# 02_LAN7800_Controller.net
KiCad netlist of a schematic drawn in Altium Designer
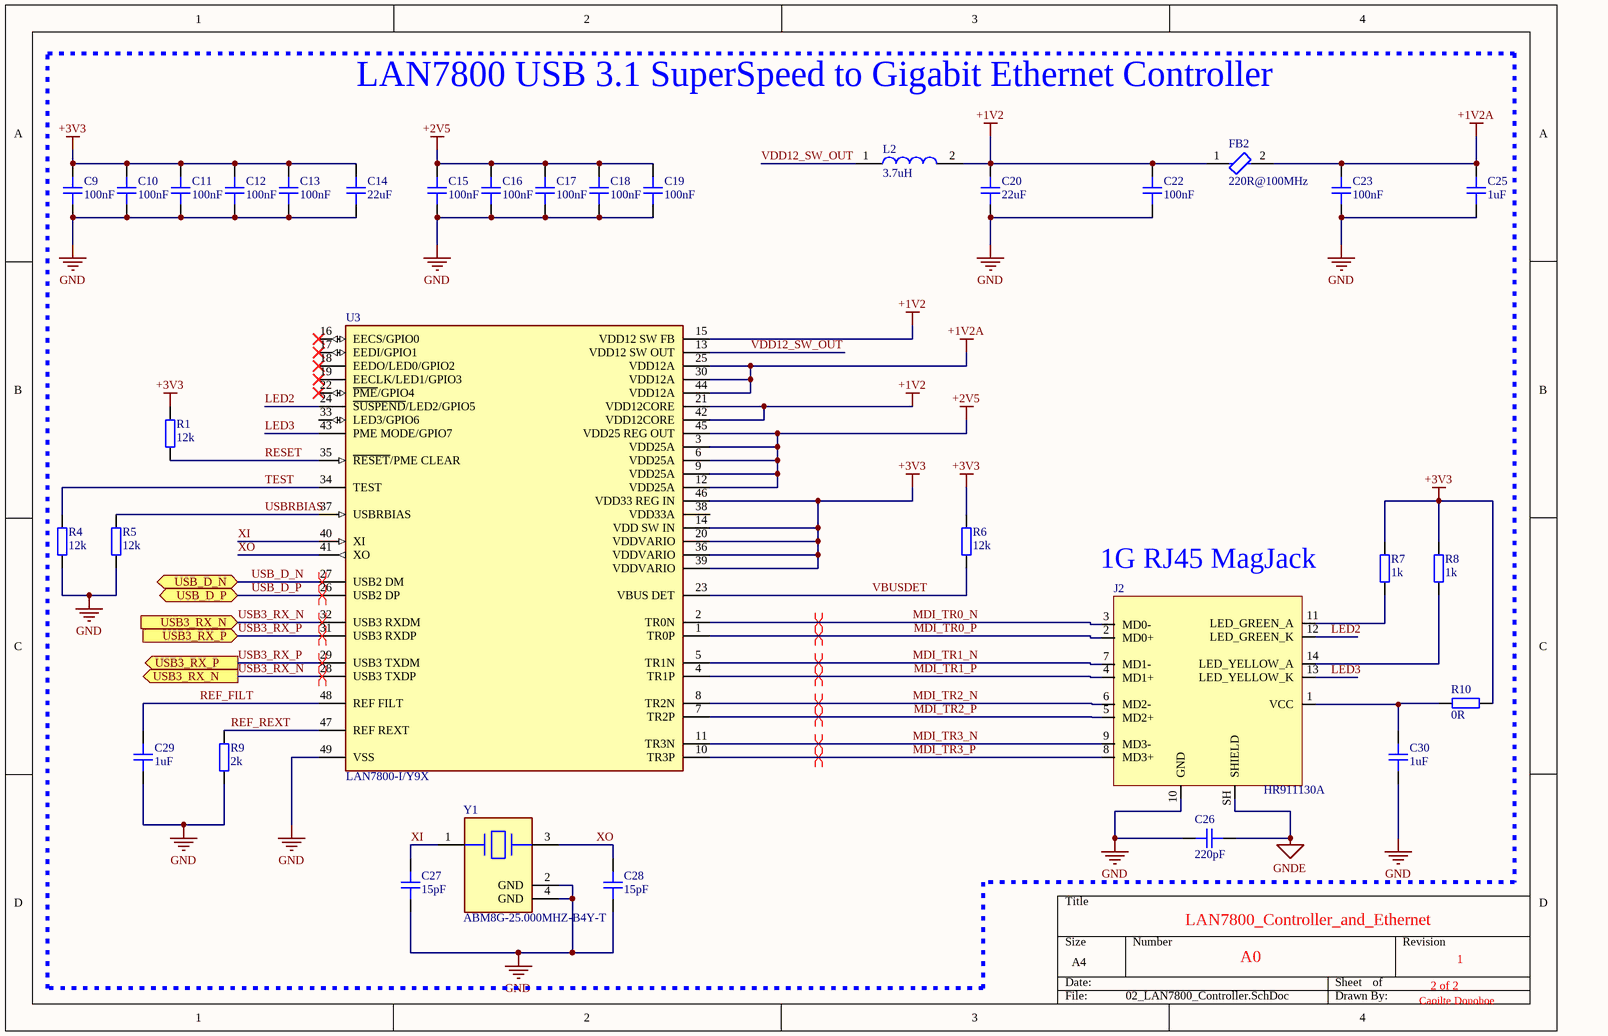
[diagram p0: 02_LAN7800_Controller.SchDoc]

(export (version "E")
  (design (tool "Eeschema 10.0.6"))
  (components
    (comp (ref "C9")
      (value "100nF")
      (footprint "CAP_0402")
      (description "Capacitor SMD 0402")
      (libsource (lib "Schematic-Lib-PMS_Caoilte") (part "CAP_0402"))
    )
    (comp (ref "C10")
      (value "100nF")
      (footprint "CAP_0402")
      (description "Capacitor SMD 0402")
      (libsource (lib "Schematic-Lib-PMS_Caoilte") (part "CAP_0402"))
    )
    (comp (ref "C11")
      (value "100nF")
      (footprint "CAP_0402")
      (description "Capacitor SMD 0402")
      (libsource (lib "Schematic-Lib-PMS_Caoilte") (part "CAP_0402"))
    )
    (comp (ref "C12")
      (value "100nF")
      (footprint "CAP_0402")
      (description "Capacitor SMD 0402")
      (libsource (lib "Schematic-Lib-PMS_Caoilte") (part "CAP_0402"))
    )
    (comp (ref "C13")
      (value "100nF")
      (footprint "CAP_0402")
      (description "Capacitor SMD 0402")
      (libsource (lib "Schematic-Lib-PMS_Caoilte") (part "CAP_0402"))
    )
    (comp (ref "C14")
      (value "22uF")
      (footprint "CAP_0603")
      (description "Capacitor SMD 0603")
      (libsource (lib "Schematic-Lib-PMS_Caoilte") (part "CAP_0603"))
    )
    (comp (ref "C15")
      (value "100nF")
      (footprint "CAP_0402")
      (description "Capacitor SMD 0402")
      (libsource (lib "Schematic-Lib-PMS_Caoilte") (part "CAP_0402"))
    )
    (comp (ref "C16")
      (value "100nF")
      (footprint "CAP_0402")
      (description "Capacitor SMD 0402")
      (libsource (lib "Schematic-Lib-PMS_Caoilte") (part "CAP_0402"))
    )
    (comp (ref "C17")
      (value "100nF")
      (footprint "CAP_0402")
      (description "Capacitor SMD 0402")
      (libsource (lib "Schematic-Lib-PMS_Caoilte") (part "CAP_0402"))
    )
    (comp (ref "C18")
      (value "100nF")
      (footprint "CAP_0402")
      (description "Capacitor SMD 0402")
      (libsource (lib "Schematic-Lib-PMS_Caoilte") (part "CAP_0402"))
    )
    (comp (ref "C19")
      (value "100nF")
      (footprint "CAP_0402")
      (description "Capacitor SMD 0402")
      (libsource (lib "Schematic-Lib-PMS_Caoilte") (part "CAP_0402"))
    )
    (comp (ref "C20")
      (value "22uF")
      (footprint "CAP_0603")
      (description "Capacitor SMD 0603")
      (libsource (lib "Schematic-Lib-PMS_Caoilte") (part "CAP_0603"))
    )
    (comp (ref "C22")
      (value "100nF")
      (footprint "CAP_0402")
      (description "Capacitor SMD 0402")
      (libsource (lib "Schematic-Lib-PMS_Caoilte") (part "CAP_0402"))
    )
    (comp (ref "C23")
      (value "100nF")
      (footprint "CAP_0402")
      (description "Capacitor SMD 0402")
      (libsource (lib "Schematic-Lib-PMS_Caoilte") (part "CAP_0402"))
    )
    (comp (ref "C25")
      (value "1uF")
      (footprint "CAP_0402")
      (description "Capacitor SMD 0402")
      (libsource (lib "Schematic-Lib-PMS_Caoilte") (part "CAP_0402"))
    )
    (comp (ref "C26")
      (value "220pF")
      (footprint "CAP_0603")
      (description "Capacitor SMD 0603")
      (libsource (lib "Schematic-Lib-PMS_Caoilte") (part "CAP_0603"))
    )
    (comp (ref "C27")
      (value "15pF")
      (footprint "CAP_0603")
      (description "Capacitor SMD 0603")
      (libsource (lib "Schematic-Lib-PMS_Caoilte") (part "CAP_0603"))
    )
    (comp (ref "C28")
      (value "15pF")
      (footprint "CAP_0603")
      (description "Capacitor SMD 0603")
      (libsource (lib "Schematic-Lib-PMS_Caoilte") (part "CAP_0603"))
    )
    (comp (ref "C29")
      (value "1uF")
      (footprint "CAP_0402")
      (description "Capacitor SMD 0402")
      (libsource (lib "Schematic-Lib-PMS_Caoilte") (part "CAP_0402"))
    )
    (comp (ref "C30")
      (value "1uF")
      (footprint "CAP_0402")
      (description "Capacitor SMD 0402")
      (libsource (lib "Schematic-Lib-PMS_Caoilte") (part "CAP_0402"))
    )
    (comp (ref "FB2")
      (value "220R@100MHz")
      (footprint "FP-BLM21-0_2-t0_85-e0_5-IPC_C")
      (description "Chip Ferrite Bead, 0805, 220Ω @ 100MHz, 0.045Ω, 25%, 2A")
      (fields (field (name "TOLERANCE") "25%"))
      (libsource (lib "LAN7800_USB_Ethernet_RevA") (part "CMP-0686-00610-3"))
    )
    (comp (ref "J2")
      (value "HR911130A")
      (footprint "HR911130A")
      (description "100/1000Base-T Magnetics Single-Port RJ45 Connector with Integrated Magnetics and LEDs")
      (fields (field (name "MANUFACTURER") "Hanrun"))
      (libsource (lib "LAN7800_USB_Ethernet_RevA") (part "HR911130A"))
    )
    (comp (ref "L2")
      (value "3.7uH")
      (footprint "SamacSys:LQM18PH1R0MFRB")
      (description "Inductor")
      (fields
        (field (name "MANUFACTURER_PART_NUMBER") "LQM18PN3R3MFRL")
        (field (name "MOUSER PART NUMBER") "81-LQM18PN3R3MFRL")
      )
      (libsource (lib "LAN7800_USB_Ethernet_RevA") (part "LQM18PN3R3MFRL"))
    )
    (comp (ref "R1")
      (value "12k")
      (footprint "RES_0402")
      (description "Resistor SMD 0402")
      (libsource (lib "Schematic-Lib-PMS_Caoilte") (part "RES_0402"))
    )
    (comp (ref "R4")
      (value "12k")
      (footprint "RES_0402")
      (description "Resistor SMD 0402")
      (libsource (lib "Schematic-Lib-PMS_Caoilte") (part "RES_0402"))
    )
    (comp (ref "R5")
      (value "12k")
      (footprint "RES_0402")
      (description "Resistor SMD 0402")
      (libsource (lib "Schematic-Lib-PMS_Caoilte") (part "RES_0402"))
    )
    (comp (ref "R6")
      (value "12k")
      (footprint "RES_0402")
      (description "Resistor SMD 0402")
      (libsource (lib "Schematic-Lib-PMS_Caoilte") (part "RES_0402"))
    )
    (comp (ref "R7")
      (value "1k")
      (footprint "RES_0402")
      (description "Resistor SMD 0402")
      (libsource (lib "Schematic-Lib-PMS_Caoilte") (part "RES_0402"))
    )
    (comp (ref "R8")
      (value "1k")
      (footprint "RES_0402")
      (description "Resistor SMD 0402")
      (libsource (lib "Schematic-Lib-PMS_Caoilte") (part "RES_0402"))
    )
    (comp (ref "R9")
      (value "2k")
      (footprint "RES_0402")
      (description "Resistor SMD 0402")
      (libsource (lib "Schematic-Lib-PMS_Caoilte") (part "RES_0402"))
    )
    (comp (ref "R10")
      (value "0R")
      (footprint "RES_0402")
      (description "Resistor SMD 0402")
      (libsource (lib "Schematic-Lib-PMS_Caoilte") (part "RES_0402"))
    )
    (comp (ref "U3")
      (value "LAN7800-I/Y9X")
      (footprint "FP-48SQFN-5304-7x7B-IPC_B")
      (description "IC ETHERNET CTLR USB 48SQFN")
      (libsource (lib "LAN7800_USB_Ethernet_RevA") (part "CMP-06298-000014-1"))
    )
    (comp (ref "Y1")
      (value "ABM8G-25.000MHZ-B4Y-T")
      (footprint "FP-ABM8G-MFG")
      (description "Crystal 25MHz ±30ppm (Tol) ±30ppm (Stability) 10pF FUND 60Ω 4-Pin SMD T/R")
      (fields (field (name "TOLERANCE") "30ppm"))
      (libsource (lib "LAN7800_USB_Ethernet_RevA") (part "CMP-27762-000021-2"))
    )
  )
  (nets
    (net (code "1") (name "+1V2") (class "Default")
      (node (ref "C20") (pin "2") (pinfunction "2_2") (pintype "passive"))
      (node (ref "C22") (pin "2") (pinfunction "2_2") (pintype "passive"))
      (node (ref "FB2") (pin "1") (pinfunction "1_1") (pintype "passive"))
      (node (ref "L2") (pin "2") (pinfunction "2_2") (pintype "passive"))
      (node (ref "U3") (pin "15") (pinfunction "VDD12_SW_FB_15") (pintype "power_in"))
      (node (ref "U3") (pin "21") (pinfunction "VDD12CORE_21") (pintype "power_in"))
      (node (ref "U3") (pin "42") (pinfunction "VDD12CORE_42") (pintype "power_in"))
    )
    (net (code "2") (name "+1V2A") (class "Default")
      (node (ref "C23") (pin "2") (pinfunction "2_2") (pintype "passive"))
      (node (ref "C25") (pin "2") (pinfunction "2_2") (pintype "passive"))
      (node (ref "FB2") (pin "2") (pinfunction "2_2") (pintype "passive"))
      (node (ref "U3") (pin "25") (pinfunction "VDD12A_25") (pintype "power_in"))
      (node (ref "U3") (pin "30") (pinfunction "VDD12A_30") (pintype "power_in"))
      (node (ref "U3") (pin "44") (pinfunction "VDD12A_44") (pintype "power_in"))
    )
    (net (code "3") (name "+2V5") (class "Default")
      (node (ref "C15") (pin "2") (pinfunction "2_2") (pintype "passive"))
      (node (ref "C16") (pin "2") (pinfunction "2_2") (pintype "passive"))
      (node (ref "C17") (pin "2") (pinfunction "2_2") (pintype "passive"))
      (node (ref "C18") (pin "2") (pinfunction "2_2") (pintype "passive"))
      (node (ref "C19") (pin "2") (pinfunction "2_2") (pintype "passive"))
      (node (ref "U3") (pin "12") (pinfunction "VDD25A_12") (pintype "power_in"))
      (node (ref "U3") (pin "3") (pinfunction "VDD25A_3") (pintype "power_in"))
      (node (ref "U3") (pin "45") (pinfunction "VDD25_REG_OUT_45") (pintype "power_in"))
      (node (ref "U3") (pin "6") (pinfunction "VDD25A_6") (pintype "power_in"))
      (node (ref "U3") (pin "9") (pinfunction "VDD25A_9") (pintype "power_in"))
    )
    (net (code "4") (name "+3V3") (class "Default")
      (node (ref "C10") (pin "2") (pinfunction "2_2") (pintype "passive"))
      (node (ref "C11") (pin "2") (pinfunction "2_2") (pintype "passive"))
      (node (ref "C12") (pin "2") (pinfunction "2_2") (pintype "passive"))
      (node (ref "C13") (pin "2") (pinfunction "2_2") (pintype "passive"))
      (node (ref "C14") (pin "2") (pinfunction "2_2") (pintype "passive"))
      (node (ref "C9") (pin "2") (pinfunction "2_2") (pintype "passive"))
      (node (ref "R1") (pin "2") (pinfunction "2_2") (pintype "passive"))
      (node (ref "R10") (pin "2") (pinfunction "2_2") (pintype "passive"))
      (node (ref "R6") (pin "1") (pinfunction "1_1") (pintype "passive"))
      (node (ref "R7") (pin "1") (pinfunction "1_1") (pintype "passive"))
      (node (ref "R8") (pin "1") (pinfunction "1_1") (pintype "passive"))
      (node (ref "U3") (pin "14") (pinfunction "VDD_SW_IN_14") (pintype "power_in"))
      (node (ref "U3") (pin "20") (pinfunction "VDDVARIO_20") (pintype "power_in"))
      (node (ref "U3") (pin "36") (pinfunction "VDDVARIO_36") (pintype "power_in"))
      (node (ref "U3") (pin "39") (pinfunction "VDDVARIO_39") (pintype "power_in"))
      (node (ref "U3") (pin "46") (pinfunction "VDD33_REG_IN_46") (pintype "power_in"))
    )
    (net (code "5") (name "/LED2") (class "Default")
      (node (ref "J2") (pin "12") (pinfunction "LED_GREEN_K_12") (pintype "passive"))
      (node (ref "U3") (pin "24") (pinfunction "~{SUSPEND}/LED2/GPIO5_24") (pintype "passive"))
    )
    (net (code "6") (name "/LED3") (class "Default")
      (node (ref "J2") (pin "13") (pinfunction "LED_YELLOW_K_13") (pintype "passive"))
      (node (ref "U3") (pin "43") (pinfunction "PME_MODE/GPIO7_43") (pintype "passive"))
    )
    (net (code "7") (name "/MDI_TR0_N") (class "Default")
      (node (ref "J2") (pin "3") (pinfunction "MD0-_3") (pintype "passive"))
      (node (ref "U3") (pin "2") (pinfunction "TR0N_2") (pintype "passive"))
    )
    (net (code "8") (name "/MDI_TR0_P") (class "Default")
      (node (ref "J2") (pin "2") (pinfunction "MD0+_2") (pintype "passive"))
      (node (ref "U3") (pin "1") (pinfunction "TR0P_1") (pintype "passive"))
    )
    (net (code "9") (name "/MDI_TR1_N") (class "Default")
      (node (ref "J2") (pin "7") (pinfunction "MD1-_7") (pintype "passive"))
      (node (ref "U3") (pin "5") (pinfunction "TR1N_5") (pintype "passive"))
    )
    (net (code "10") (name "/MDI_TR1_P") (class "Default")
      (node (ref "J2") (pin "4") (pinfunction "MD1+_4") (pintype "passive"))
      (node (ref "U3") (pin "4") (pinfunction "TR1P_4") (pintype "passive"))
    )
    (net (code "11") (name "/MDI_TR2_N") (class "Default")
      (node (ref "J2") (pin "6") (pinfunction "MD2-_6") (pintype "passive"))
      (node (ref "U3") (pin "8") (pinfunction "TR2N_8") (pintype "passive"))
    )
    (net (code "12") (name "/MDI_TR2_P") (class "Default")
      (node (ref "J2") (pin "5") (pinfunction "MD2+_5") (pintype "passive"))
      (node (ref "U3") (pin "7") (pinfunction "TR2P_7") (pintype "passive"))
    )
    (net (code "13") (name "/MDI_TR3_N") (class "Default")
      (node (ref "J2") (pin "9") (pinfunction "MD3-_9") (pintype "passive"))
      (node (ref "U3") (pin "11") (pinfunction "TR3N_11") (pintype "passive"))
    )
    (net (code "14") (name "/MDI_TR3_P") (class "Default")
      (node (ref "J2") (pin "8") (pinfunction "MD3+_8") (pintype "passive"))
      (node (ref "U3") (pin "10") (pinfunction "TR3P_10") (pintype "passive"))
    )
    (net (code "15") (name "/REF_FILT") (class "Default")
      (node (ref "C29") (pin "2") (pinfunction "2_2") (pintype "passive"))
      (node (ref "U3") (pin "48") (pinfunction "REF_FILT_48") (pintype "passive"))
    )
    (net (code "16") (name "/REF_REXT") (class "Default")
      (node (ref "R9") (pin "2") (pinfunction "2_2") (pintype "passive"))
      (node (ref "U3") (pin "47") (pinfunction "REF_REXT_47") (pintype "passive"))
    )
    (net (code "17") (name "/RESET") (class "Default")
      (node (ref "R1") (pin "1") (pinfunction "1_1") (pintype "passive"))
      (node (ref "U3") (pin "35") (pinfunction "~{RESET}/PME_CLEAR_35") (pintype "input"))
    )
    (net (code "18") (name "/TEST") (class "Default")
      (node (ref "R4") (pin "2") (pinfunction "2_2") (pintype "passive"))
      (node (ref "U3") (pin "34") (pinfunction "TEST_34") (pintype "passive"))
    )
    (net (code "19") (name "/USB3_RX_N") (class "Default")
      (node (ref "U3") (pin "28") (pinfunction "USB3_TXDP_28") (pintype "passive"))
      (node (ref "U3") (pin "32") (pinfunction "USB3_RXDM_32") (pintype "passive"))
    )
    (net (code "20") (name "/USB3_RX_P") (class "Default")
      (node (ref "U3") (pin "29") (pinfunction "USB3_TXDM_29") (pintype "passive"))
      (node (ref "U3") (pin "31") (pinfunction "USB3_RXDP_31") (pintype "passive"))
    )
    (net (code "21") (name "/USBRBIAS") (class "Default")
      (node (ref "R5") (pin "2") (pinfunction "2_2") (pintype "passive"))
      (node (ref "U3") (pin "37") (pinfunction "USBRBIAS_37") (pintype "input"))
    )
    (net (code "22") (name "/USB_D_N") (class "Default")
      (node (ref "U3") (pin "27") (pinfunction "USB2_DM_27") (pintype "passive"))
    )
    (net (code "23") (name "/USB_D_P") (class "Default")
      (node (ref "U3") (pin "26") (pinfunction "USB2_DP_26") (pintype "passive"))
    )
    (net (code "24") (name "/VBUSDET") (class "Default")
      (node (ref "R6") (pin "2") (pinfunction "2_2") (pintype "passive"))
      (node (ref "U3") (pin "23") (pinfunction "VBUS_DET_23") (pintype "power_in"))
    )
    (net (code "25") (name "/VDD12_SW_OUT") (class "Default")
      (node (ref "L2") (pin "1") (pinfunction "1_1") (pintype "passive"))
      (node (ref "U3") (pin "13") (pinfunction "VDD12_SW_OUT_13") (pintype "power_in"))
    )
    (net (code "26") (name "/XI") (class "Default")
      (node (ref "C27") (pin "2") (pinfunction "2_2") (pintype "passive"))
      (node (ref "U3") (pin "40") (pinfunction "XI_40") (pintype "input"))
      (node (ref "Y1") (pin "1") (pinfunction "1_1") (pintype "passive"))
    )
    (net (code "27") (name "/XO") (class "Default")
      (node (ref "C28") (pin "2") (pinfunction "2_2") (pintype "passive"))
      (node (ref "U3") (pin "41") (pinfunction "XO_41") (pintype "output"))
      (node (ref "Y1") (pin "3") (pinfunction "3_3") (pintype "passive"))
    )
    (net (code "28") (name "GND") (class "Default")
      (node (ref "C10") (pin "1") (pinfunction "1_1") (pintype "passive"))
      (node (ref "C11") (pin "1") (pinfunction "1_1") (pintype "passive"))
      (node (ref "C12") (pin "1") (pinfunction "1_1") (pintype "passive"))
      (node (ref "C13") (pin "1") (pinfunction "1_1") (pintype "passive"))
      (node (ref "C14") (pin "1") (pinfunction "1_1") (pintype "passive"))
      (node (ref "C15") (pin "1") (pinfunction "1_1") (pintype "passive"))
      (node (ref "C16") (pin "1") (pinfunction "1_1") (pintype "passive"))
      (node (ref "C17") (pin "1") (pinfunction "1_1") (pintype "passive"))
      (node (ref "C18") (pin "1") (pinfunction "1_1") (pintype "passive"))
      (node (ref "C19") (pin "1") (pinfunction "1_1") (pintype "passive"))
      (node (ref "C20") (pin "1") (pinfunction "1_1") (pintype "passive"))
      (node (ref "C22") (pin "1") (pinfunction "1_1") (pintype "passive"))
      (node (ref "C23") (pin "1") (pinfunction "1_1") (pintype "passive"))
      (node (ref "C25") (pin "1") (pinfunction "1_1") (pintype "passive"))
      (node (ref "C26") (pin "1") (pinfunction "1_1") (pintype "passive"))
      (node (ref "C27") (pin "1") (pinfunction "1_1") (pintype "passive"))
      (node (ref "C28") (pin "1") (pinfunction "1_1") (pintype "passive"))
      (node (ref "C29") (pin "1") (pinfunction "1_1") (pintype "passive"))
      (node (ref "C30") (pin "1") (pinfunction "1_1") (pintype "passive"))
      (node (ref "C9") (pin "1") (pinfunction "1_1") (pintype "passive"))
      (node (ref "J2") (pin "10") (pinfunction "GND_10") (pintype "passive"))
      (node (ref "R4") (pin "1") (pinfunction "1_1") (pintype "passive"))
      (node (ref "R5") (pin "1") (pinfunction "1_1") (pintype "passive"))
      (node (ref "R9") (pin "1") (pinfunction "1_1") (pintype "passive"))
      (node (ref "U3") (pin "49") (pinfunction "VSS_49") (pintype "power_in"))
      (node (ref "Y1") (pin "2") (pinfunction "GND_2") (pintype "power_in"))
      (node (ref "Y1") (pin "4") (pinfunction "GND_4") (pintype "power_in"))
    )
    (net (code "29") (name "GNDE") (class "Default")
      (node (ref "C26") (pin "2") (pinfunction "2_2") (pintype "passive"))
      (node (ref "J2") (pin "SH") (pinfunction "SHIELD_SH") (pintype "passive"))
    )
    (net (code "30") (name "Net-(J2-LED_GREEN_A)") (class "Default")
      (node (ref "J2") (pin "11") (pinfunction "LED_GREEN_A_11") (pintype "passive"))
      (node (ref "R7") (pin "2") (pinfunction "2_2") (pintype "passive"))
    )
    (net (code "31") (name "Net-(J2-LED_YELLOW_A)") (class "Default")
      (node (ref "J2") (pin "14") (pinfunction "LED_YELLOW_A_14") (pintype "passive"))
      (node (ref "R8") (pin "2") (pinfunction "2_2") (pintype "passive"))
    )
    (net (code "32") (name "Net-(J2-VCC)") (class "Default")
      (node (ref "C30") (pin "2") (pinfunction "2_2") (pintype "passive"))
      (node (ref "J2") (pin "1") (pinfunction "VCC_1") (pintype "passive"))
      (node (ref "R10") (pin "1") (pinfunction "1_1") (pintype "passive"))
    )
    (net (code "33") (name "unconnected-(U3-EECLK{slash}LED1{slash}GPIO3-Pad19)") (class "Default")
      (node (ref "U3") (pin "19") (pinfunction "EECLK/LED1/GPIO3_19") (pintype "passive+no_connect"))
    )
    (net (code "34") (name "unconnected-(U3-EECS{slash}GPIO0-Pad16)") (class "Default")
      (node (ref "U3") (pin "16") (pinfunction "EECS/GPIO0_16") (pintype "bidirectional+no_connect"))
    )
    (net (code "35") (name "unconnected-(U3-EEDI{slash}GPIO1-Pad17)") (class "Default")
      (node (ref "U3") (pin "17") (pinfunction "EEDI/GPIO1_17") (pintype "bidirectional+no_connect"))
    )
    (net (code "36") (name "unconnected-(U3-EEDO{slash}LED0{slash}GPIO2-Pad18)") (class "Default")
      (node (ref "U3") (pin "18") (pinfunction "EEDO/LED0/GPIO2_18") (pintype "passive+no_connect"))
    )
    (net (code "37") (name "unconnected-(U3-LED3{slash}GPIO6-Pad33)") (class "Default")
      (node (ref "U3") (pin "33") (pinfunction "LED3/GPIO6_33") (pintype "bidirectional"))
    )
    (net (code "38") (name "unconnected-(U3-VDD33A-Pad38)") (class "Default")
      (node (ref "U3") (pin "38") (pinfunction "VDD33A_38") (pintype "power_in"))
    )
    (net (code "39") (name "unconnected-(U3-~{PME}{slash}GPIO4-Pad22)") (class "Default")
      (node (ref "U3") (pin "22") (pinfunction "~{PME}/GPIO4_22") (pintype "bidirectional+no_connect"))
    )
  )
)
